# TPS26630_test.net
KiCad netlist of a schematic drawn in EAGLE
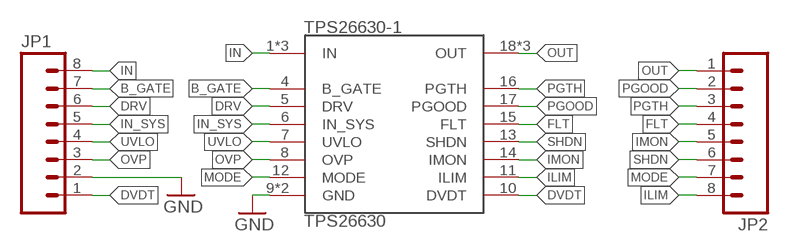
[diagram p0: schematic, sheet 1]

(export (version "E")
  (design (tool "Eeschema 10.0.6"))
  (components
    (comp (ref "JP1")
      (value "M08")
      (footprint "eagle-import:1X08")
      (libsource (lib "eagle-import") (part "M08"))
    )
    (comp (ref "JP2")
      (value "M08")
      (footprint "eagle-import:1X08")
      (libsource (lib "eagle-import") (part "M08"))
    )
    (comp (ref "TPS26630-1")
      (value "TPS26630")
      (footprint "eagle-import:HTSSOP-20")
      (libsource (lib "eagle-import") (part "TPS26630"))
    )
  )
  (nets
    (net (code "1") (name "B_GATE") (class "Default")
      (node (ref "JP1") (pin "7") (pinfunction "7_7") (pintype "passive"))
      (node (ref "TPS26630-1") (pin "4") (pinfunction "B_GATE_4") (pintype "bidirectional"))
    )
    (net (code "2") (name "DRV") (class "Default")
      (node (ref "JP1") (pin "6") (pinfunction "6_6") (pintype "passive"))
      (node (ref "TPS26630-1") (pin "5") (pinfunction "DRV_5") (pintype "bidirectional"))
    )
    (net (code "3") (name "DVDT") (class "Default")
      (node (ref "JP1") (pin "1") (pinfunction "1_1") (pintype "passive"))
      (node (ref "TPS26630-1") (pin "10") (pinfunction "DVDT_10") (pintype "bidirectional"))
    )
    (net (code "4") (name "FLT") (class "Default")
      (node (ref "JP2") (pin "4") (pinfunction "4_4") (pintype "passive"))
      (node (ref "TPS26630-1") (pin "15") (pinfunction "FLT_15") (pintype "bidirectional"))
    )
    (net (code "5") (name "GND") (class "Default")
      (node (ref "JP1") (pin "2") (pinfunction "2_2") (pintype "passive"))
      (node (ref "TPS26630-1") (pin "9") (pinfunction "GND_9") (pintype "bidirectional"))
      (node (ref "TPS26630-1") (pin "PAD") (pinfunction "GND_PAD") (pintype "bidirectional"))
    )
    (net (code "6") (name "ILIM") (class "Default")
      (node (ref "JP2") (pin "8") (pinfunction "8_8") (pintype "passive"))
      (node (ref "TPS26630-1") (pin "11") (pinfunction "ILIM_11") (pintype "bidirectional"))
    )
    (net (code "7") (name "IMON") (class "Default")
      (node (ref "JP2") (pin "5") (pinfunction "5_5") (pintype "passive"))
      (node (ref "TPS26630-1") (pin "14") (pinfunction "IMON_14") (pintype "bidirectional"))
    )
    (net (code "8") (name "IN") (class "Default")
      (node (ref "JP1") (pin "8") (pinfunction "8_8") (pintype "passive"))
      (node (ref "TPS26630-1") (pin "1") (pinfunction "IN_1") (pintype "bidirectional"))
      (node (ref "TPS26630-1") (pin "2") (pinfunction "IN_2") (pintype "bidirectional"))
      (node (ref "TPS26630-1") (pin "3") (pinfunction "IN_3") (pintype "bidirectional"))
    )
    (net (code "9") (name "IN_SYS") (class "Default")
      (node (ref "JP1") (pin "5") (pinfunction "5_5") (pintype "passive"))
      (node (ref "TPS26630-1") (pin "6") (pinfunction "IN_SYS_6") (pintype "bidirectional"))
    )
    (net (code "10") (name "MODE") (class "Default")
      (node (ref "JP2") (pin "7") (pinfunction "7_7") (pintype "passive"))
      (node (ref "TPS26630-1") (pin "12") (pinfunction "MODE_12") (pintype "bidirectional"))
    )
    (net (code "11") (name "OUT") (class "Default")
      (node (ref "JP2") (pin "1") (pinfunction "1_1") (pintype "passive"))
      (node (ref "TPS26630-1") (pin "18") (pinfunction "OUT_18") (pintype "bidirectional"))
      (node (ref "TPS26630-1") (pin "19") (pinfunction "OUT_19") (pintype "bidirectional"))
      (node (ref "TPS26630-1") (pin "20") (pinfunction "OUT_20") (pintype "bidirectional"))
    )
    (net (code "12") (name "OVP") (class "Default")
      (node (ref "JP1") (pin "3") (pinfunction "3_3") (pintype "passive"))
      (node (ref "TPS26630-1") (pin "8") (pinfunction "OVP_8") (pintype "bidirectional"))
    )
    (net (code "13") (name "PGOOD") (class "Default")
      (node (ref "JP2") (pin "2") (pinfunction "2_2") (pintype "passive"))
      (node (ref "TPS26630-1") (pin "17") (pinfunction "PGOOD_17") (pintype "bidirectional"))
    )
    (net (code "14") (name "PGTH") (class "Default")
      (node (ref "JP2") (pin "3") (pinfunction "3_3") (pintype "passive"))
      (node (ref "TPS26630-1") (pin "16") (pinfunction "PGTH_16") (pintype "bidirectional"))
    )
    (net (code "15") (name "SHDN") (class "Default")
      (node (ref "JP2") (pin "6") (pinfunction "6_6") (pintype "passive"))
      (node (ref "TPS26630-1") (pin "13") (pinfunction "SHDN_13") (pintype "bidirectional"))
    )
    (net (code "16") (name "UVLO") (class "Default")
      (node (ref "JP1") (pin "4") (pinfunction "4_4") (pintype "passive"))
      (node (ref "TPS26630-1") (pin "7") (pinfunction "UVLO_7") (pintype "bidirectional"))
    )
  )
)
